# 04_-_POWER_HARVESTING_SYSTEM.net
KiCad netlist of a schematic drawn in Altium Designer
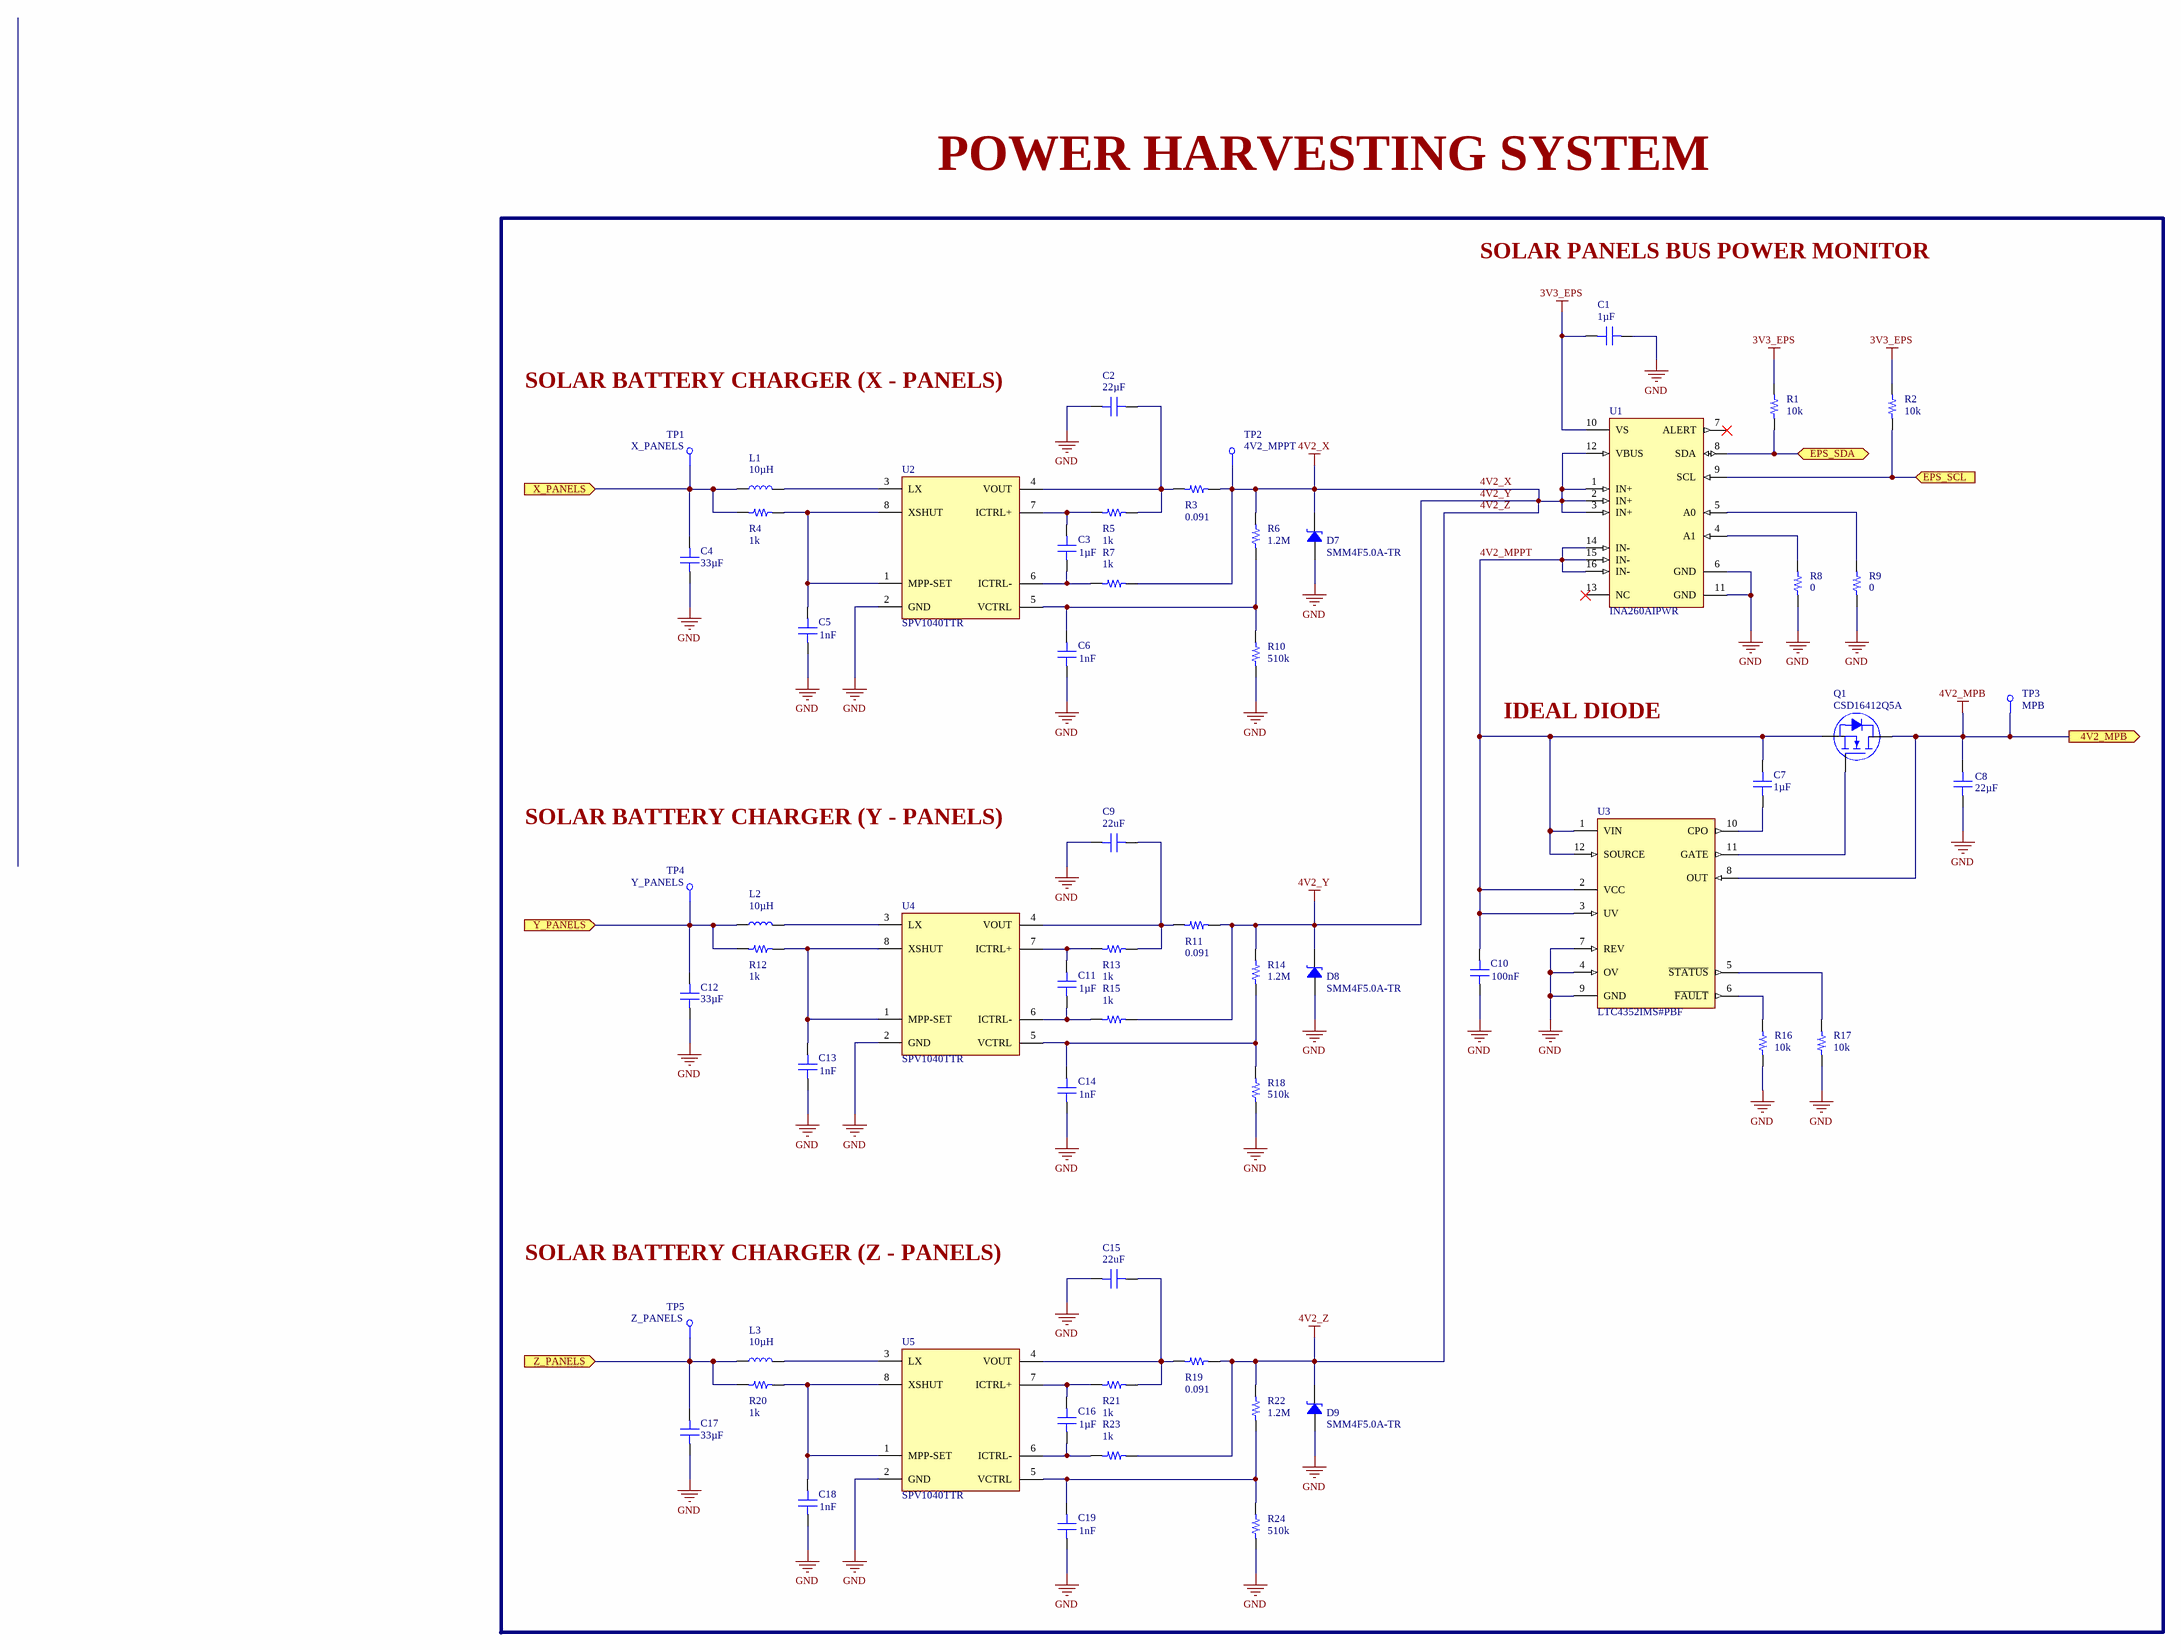
[diagram p0: [04] - POWER HARVESTING SYSTEM.SchDoc]

(export (version "E")
  (design (tool "Eeschema 10.0.6"))
  (components
    (comp (ref "C1")
      (value "CL10A105KP8NNNC")
      (footprint "CAP 0603/1608")
      (description "CAP CER 1UF 10V X5R 0603")
      (fields
        (field (name "MANUFACTURER") "Samsung")
        (field (name "TOLERANCE") "10%")
        (field (name "CAPACITANCE") "1µF")
      )
      (libsource (lib "UVG") (part "CL10A105KP8NNNC"))
    )
    (comp (ref "C2")
      (value "CL21A226MQQNNNE")
      (footprint "CAP 0805/2012")
      (description "CAP CER 22UF 6.3V X5R 0805")
      (fields
        (field (name "MANUFACTURER") "Samsung")
        (field (name "CAPACITANCE") "22µF")
        (field (name "TOLERANCE") "20%")
      )
      (libsource (lib "UVG") (part "CL21A226MQQNNNE"))
    )
    (comp (ref "C3")
      (value "CL10A105KP8NNNC")
      (footprint "CAP 0603/1608")
      (description "CAP CER 1UF 10V X5R 0603")
      (fields
        (field (name "MANUFACTURER") "Samsung")
        (field (name "TOLERANCE") "10%")
        (field (name "CAPACITANCE") "1µF")
      )
      (libsource (lib "UVG") (part "CL10A105KP8NNNC"))
    )
    (comp (ref "C4")
      (value "GRM21BR60G336ME15L")
      (footprint "CAP 0805/2012")
      (description "CAP CER 33UF 4V X5R 0805")
      (fields
        (field (name "MANUFACTURER") "Murata")
        (field (name "TOLERANCE") "20%")
        (field (name "CAPACITANCE") "33µF")
      )
      (libsource (lib "UVG") (part "GRM21BR60G336ME15L"))
    )
    (comp (ref "C5")
      (value "CL10C102JB8NNNC")
      (footprint "CAP 0603/1608")
      (description "CAP CER 1000PF 50V C0G/NP0 0603")
      (fields
        (field (name "MANUFACTURER") "Samsung")
        (field (name "TOLERANCE") "5%")
        (field (name "CAPACITANCE") "1nF")
      )
      (libsource (lib "UVG") (part "CL10C102JB8NNNC"))
    )
    (comp (ref "C6")
      (value "CL10C102JB8NNNC")
      (footprint "CAP 0603/1608")
      (description "CAP CER 1000PF 50V C0G/NP0 0603")
      (fields
        (field (name "MANUFACTURER") "Samsung")
        (field (name "TOLERANCE") "5%")
        (field (name "CAPACITANCE") "1nF")
      )
      (libsource (lib "UVG") (part "CL10C102JB8NNNC"))
    )
    (comp (ref "C7")
      (value "CL10A105KP8NNNC")
      (footprint "CAP 0603/1608")
      (description "CAP CER 1UF 10V X5R 0603")
      (fields
        (field (name "MANUFACTURER") "Samsung")
        (field (name "TOLERANCE") "10%")
        (field (name "CAPACITANCE") "1µF")
      )
      (libsource (lib "UVG") (part "CL10A105KP8NNNC"))
    )
    (comp (ref "C8")
      (value "GRM188R60J226MEA0D")
      (footprint "CAP 0603/1608")
      (description "CAP CER 22UF 6.3V X5R 0603")
      (fields
        (field (name "MANUFACTURER") "Murata")
        (field (name "CAPACITANCE") "22µF")
        (field (name "TOLERANCE") "20%")
      )
      (libsource (lib "UVG") (part "GRM188R60J226MEA0D"))
    )
    (comp (ref "C9")
      (value "CL21A226MQQNNNE")
      (footprint "CAP 0805/2012")
      (description "CAP CER 22UF 6.3V X5R 0805")
      (fields
        (field (name "MANUFACTURER") "Samsung")
        (field (name "CAPACITANCE") "22uF")
        (field (name "TOLERANCE") "20%")
      )
      (libsource (lib "UVG") (part "CL21A226MQQNNNE"))
    )
    (comp (ref "C10")
      (value "C0603C104K8RACTU")
      (footprint "CAP 0603/1608")
      (description "CAP CER 0.1UF 10V X7R 0603")
      (fields
        (field (name "MANUFACTURER") "KEMET")
        (field (name "CAPACITANCE") "100nF")
        (field (name "TOLERANCE") "10%")
      )
      (libsource (lib "UVG") (part "C0603C104K8RACTU"))
    )
    (comp (ref "C11")
      (value "CL10A105KP8NNNC")
      (footprint "CAP 0603/1608")
      (description "CAP CER 1UF 10V X5R 0603")
      (fields
        (field (name "MANUFACTURER") "Samsung")
        (field (name "TOLERANCE") "10%")
        (field (name "CAPACITANCE") "1µF")
      )
      (libsource (lib "UVG") (part "CL10A105KP8NNNC"))
    )
    (comp (ref "C12")
      (value "GRM21BR60G336ME15L")
      (footprint "CAP 0805/2012")
      (description "CAP CER 33UF 4V X5R 0805")
      (fields
        (field (name "MANUFACTURER") "Murata")
        (field (name "TOLERANCE") "20%")
        (field (name "CAPACITANCE") "33µF")
      )
      (libsource (lib "UVG") (part "GRM21BR60G336ME15L"))
    )
    (comp (ref "C13")
      (value "CL10C102JB8NNNC")
      (footprint "CAP 0603/1608")
      (description "CAP CER 1000PF 50V C0G/NP0 0603")
      (fields
        (field (name "MANUFACTURER") "Samsung")
        (field (name "TOLERANCE") "5%")
        (field (name "CAPACITANCE") "1nF")
      )
      (libsource (lib "UVG") (part "CL10C102JB8NNNC"))
    )
    (comp (ref "C14")
      (value "CL10C102JB8NNNC")
      (footprint "CAP 0603/1608")
      (description "CAP CER 1000PF 50V C0G/NP0 0603")
      (fields
        (field (name "MANUFACTURER") "Samsung")
        (field (name "TOLERANCE") "5%")
        (field (name "CAPACITANCE") "1nF")
      )
      (libsource (lib "UVG") (part "CL10C102JB8NNNC"))
    )
    (comp (ref "C15")
      (value "CL21A226MQQNNNE")
      (footprint "CAP 0805/2012")
      (description "CAP CER 22UF 6.3V X5R 0805")
      (fields
        (field (name "MANUFACTURER") "Samsung")
        (field (name "CAPACITANCE") "22uF")
        (field (name "TOLERANCE") "20%")
      )
      (libsource (lib "UVG") (part "CL21A226MQQNNNE"))
    )
    (comp (ref "C16")
      (value "CL10A105KP8NNNC")
      (footprint "CAP 0603/1608")
      (description "CAP CER 1UF 10V X5R 0603")
      (fields
        (field (name "MANUFACTURER") "Samsung")
        (field (name "TOLERANCE") "10%")
        (field (name "CAPACITANCE") "1µF")
      )
      (libsource (lib "UVG") (part "CL10A105KP8NNNC"))
    )
    (comp (ref "C17")
      (value "GRM21BR60G336ME15L")
      (footprint "CAP 0805/2012")
      (description "CAP CER 33UF 4V X5R 0805")
      (fields
        (field (name "MANUFACTURER") "Murata")
        (field (name "TOLERANCE") "20%")
        (field (name "CAPACITANCE") "33µF")
      )
      (libsource (lib "UVG") (part "GRM21BR60G336ME15L"))
    )
    (comp (ref "C18")
      (value "CL10C102JB8NNNC")
      (footprint "CAP 0603/1608")
      (description "CAP CER 1000PF 50V C0G/NP0 0603")
      (fields
        (field (name "MANUFACTURER") "Samsung")
        (field (name "TOLERANCE") "5%")
        (field (name "CAPACITANCE") "1nF")
      )
      (libsource (lib "UVG") (part "CL10C102JB8NNNC"))
    )
    (comp (ref "C19")
      (value "CL10C102JB8NNNC")
      (footprint "CAP 0603/1608")
      (description "CAP CER 1000PF 50V C0G/NP0 0603")
      (fields
        (field (name "MANUFACTURER") "Samsung")
        (field (name "TOLERANCE") "5%")
        (field (name "CAPACITANCE") "1nF")
      )
      (libsource (lib "UVG") (part "CL10C102JB8NNNC"))
    )
    (comp (ref "D7")
      (value "SMM4F5.0A-TR")
      (footprint "DO216-AA")
      (description "Diode TVS Single Uni-Dir 5V 400W 2-Pin DO-222AA T/R")
      (fields (field (name "MANUFACTURER") "STMicroelectronics"))
      (libsource (lib "UVG") (part "SMM4F5.0A-TR"))
    )
    (comp (ref "D8")
      (value "SMM4F5.0A-TR")
      (footprint "DO216-AA")
      (description "Diode TVS Single Uni-Dir 5V 400W 2-Pin DO-222AA T/R")
      (fields (field (name "MANUFACTURER") "STMicroelectronics"))
      (libsource (lib "UVG") (part "SMM4F5.0A-TR"))
    )
    (comp (ref "D9")
      (value "SMM4F5.0A-TR")
      (footprint "DO216-AA")
      (description "Diode TVS Single Uni-Dir 5V 400W 2-Pin DO-222AA T/R")
      (fields (field (name "MANUFACTURER") "STMicroelectronics"))
      (libsource (lib "UVG") (part "SMM4F5.0A-TR"))
    )
    (comp (ref "L1")
      (value "SRR1206-100ML")
      (footprint "SRR1206")
      (description "FIXED IND 10UH 3.3A 35 MOHM SMD")
      (fields
        (field (name "MANUFACTURER") "Bourns")
        (field (name "TOLERANCE") "20%")
        (field (name "INDUCTANCE") "10µH")
      )
      (libsource (lib "UVG") (part "SRR1206-100ML"))
    )
    (comp (ref "L2")
      (value "SRR1206-100ML")
      (footprint "SRR1206")
      (description "FIXED IND 10UH 3.3A 35 MOHM SMD")
      (fields
        (field (name "MANUFACTURER") "Bourns")
        (field (name "TOLERANCE") "20%")
        (field (name "INDUCTANCE") "10µH")
      )
      (libsource (lib "UVG") (part "SRR1206-100ML"))
    )
    (comp (ref "L3")
      (value "SRR1206-100ML")
      (footprint "SRR1206")
      (description "FIXED IND 10UH 3.3A 35 MOHM SMD")
      (fields
        (field (name "MANUFACTURER") "Bourns")
        (field (name "TOLERANCE") "20%")
        (field (name "INDUCTANCE") "10µH")
      )
      (libsource (lib "UVG") (part "SRR1206-100ML"))
    )
    (comp (ref "Q1")
      (value "CSD16412Q5A")
      (footprint "8-VSONP (5x6)")
      (description "MOSFET N-CH 25V 52A 8SON")
      (fields (field (name "MANUFACTURER") "Texas Instruments"))
      (libsource (lib "UVG") (part "CSD16412Q5A"))
    )
    (comp (ref "R1")
      (value "RNCP0603FTD10K0")
      (footprint "RES 0603/1608")
      (description "RES SMD 10K OHM 1% 1/8W 0603")
      (fields
        (field (name "MANUFACTURER") "Stackpole Electronics")
        (field (name "RESISTANCE") "10k")
        (field (name "TOLERANCE") "1%")
      )
      (libsource (lib "UVG") (part "RNCP0603FTD10K0"))
    )
    (comp (ref "R2")
      (value "RNCP0603FTD10K0")
      (footprint "RES 0603/1608")
      (description "RES SMD 10K OHM 1% 1/8W 0603")
      (fields
        (field (name "MANUFACTURER") "Stackpole Electronics")
        (field (name "RESISTANCE") "10k")
        (field (name "TOLERANCE") "1%")
      )
      (libsource (lib "UVG") (part "RNCP0603FTD10K0"))
    )
    (comp (ref "R3")
      (value "RLP73N3AR091FTDF")
      (footprint "STACKPOLE CSRN2512")
      (description "RES SMD 0.091 OHM 1% 2W 2512")
      (fields
        (field (name "MANUFACTURER") "TE Connectivity")
        (field (name "MANUFACTURER PART NUMBER") "2-2176057-4")
        (field (name "RESISTANCE") "0.091")
      )
      (libsource (lib "UVG") (part "RLP73N3AR091FTDF"))
    )
    (comp (ref "R4")
      (value "ESR03EZPJ102")
      (footprint "RES 0603/1608")
      (description "RES SMD 1K OHM 5% 1/4W 0603")
      (fields
        (field (name "MANUFACTURER") "Rohm")
        (field (name "RESISTANCE") "1k")
        (field (name "TOLERANCE") "5%")
      )
      (libsource (lib "UVG") (part "ESR03EZPJ102"))
    )
    (comp (ref "R5")
      (value "ESR03EZPJ102")
      (footprint "RES 0603/1608")
      (description "RES SMD 1K OHM 5% 1/4W 0603")
      (fields
        (field (name "MANUFACTURER") "Rohm")
        (field (name "RESISTANCE") "1k")
        (field (name "TOLERANCE") "5%")
      )
      (libsource (lib "UVG") (part "ESR03EZPJ102"))
    )
    (comp (ref "R6")
      (value "RC0603JR-071M2L")
      (footprint "RES 0603/1608")
      (description "RES SMD 1.2M OHM 5% 1/10W 0603")
      (fields
        (field (name "MANUFACTURER") "Yageo")
        (field (name "RESISTANCE") "1.2M")
        (field (name "TOLERANCE") "5%")
      )
      (libsource (lib "UVG") (part "RC0603JR-071M2L"))
    )
    (comp (ref "R7")
      (value "ESR03EZPJ102")
      (footprint "RES 0603/1608")
      (description "RES SMD 1K OHM 5% 1/4W 0603")
      (fields
        (field (name "MANUFACTURER") "Rohm")
        (field (name "RESISTANCE") "1k")
        (field (name "TOLERANCE") "5%")
      )
      (libsource (lib "UVG") (part "ESR03EZPJ102"))
    )
    (comp (ref "R8")
      (value "RMCF0603ZT0R00")
      (footprint "RES 0603/1608")
      (description "RES SMD 0 OHM JUMPER 1/10W 0603")
      (fields (field (name "MANUFACTURER") "Stackpole Electronics") (field (name "RESISTANCE") "0"))
      (libsource (lib "UVG") (part "RMCF0603ZT0R00"))
    )
    (comp (ref "R9")
      (value "RMCF0603ZT0R00")
      (footprint "RES 0603/1608")
      (description "RES SMD 0 OHM JUMPER 1/10W 0603")
      (fields (field (name "MANUFACTURER") "Stackpole Electronics") (field (name "RESISTANCE") "0"))
      (libsource (lib "UVG") (part "RMCF0603ZT0R00"))
    )
    (comp (ref "R10")
      (value "RMCF0603FT510K")
      (footprint "RES 0603/1608")
      (description "RES SMD 510K OHM 1% 1/10W 0603")
      (fields
        (field (name "MANUFACTURER") "Stackpole Electronics")
        (field (name "RESISTANCE") "510k")
        (field (name "TOLERANCE") "1%")
      )
      (libsource (lib "UVG") (part "RMCF0603FT510K"))
    )
    (comp (ref "R11")
      (value "RLP73N3AR091FTDF")
      (footprint "STACKPOLE CSRN2512")
      (description "RES SMD 0.091 OHM 1% 2W 2512")
      (fields
        (field (name "MANUFACTURER") "TE Connectivity")
        (field (name "MANUFACTURER PART NUMBER") "2-2176057-4")
        (field (name "RESISTANCE") "0.091")
      )
      (libsource (lib "UVG") (part "RLP73N3AR091FTDF"))
    )
    (comp (ref "R12")
      (value "ESR03EZPJ102")
      (footprint "RES 0603/1608")
      (description "RES SMD 1K OHM 5% 1/4W 0603")
      (fields
        (field (name "MANUFACTURER") "Rohm")
        (field (name "RESISTANCE") "1k")
        (field (name "TOLERANCE") "5%")
      )
      (libsource (lib "UVG") (part "ESR03EZPJ102"))
    )
    (comp (ref "R13")
      (value "ESR03EZPJ102")
      (footprint "RES 0603/1608")
      (description "RES SMD 1K OHM 5% 1/4W 0603")
      (fields
        (field (name "MANUFACTURER") "Rohm")
        (field (name "RESISTANCE") "1k")
        (field (name "TOLERANCE") "5%")
      )
      (libsource (lib "UVG") (part "ESR03EZPJ102"))
    )
    (comp (ref "R14")
      (value "RC0603JR-071M2L")
      (footprint "RES 0603/1608")
      (description "RES SMD 1.2M OHM 5% 1/10W 0603")
      (fields
        (field (name "MANUFACTURER") "Yageo")
        (field (name "RESISTANCE") "1.2M")
        (field (name "TOLERANCE") "5%")
      )
      (libsource (lib "UVG") (part "RC0603JR-071M2L"))
    )
    (comp (ref "R15")
      (value "ESR03EZPJ102")
      (footprint "RES 0603/1608")
      (description "RES SMD 1K OHM 5% 1/4W 0603")
      (fields
        (field (name "MANUFACTURER") "Rohm")
        (field (name "RESISTANCE") "1k")
        (field (name "TOLERANCE") "5%")
      )
      (libsource (lib "UVG") (part "ESR03EZPJ102"))
    )
    (comp (ref "R16")
      (value "RNCP0603FTD10K0")
      (footprint "RES 0603/1608")
      (description "RES SMD 10K OHM 1% 1/8W 0603")
      (fields
        (field (name "MANUFACTURER") "Stackpole Electronics")
        (field (name "RESISTANCE") "10k")
        (field (name "TOLERANCE") "1%")
      )
      (libsource (lib "UVG") (part "RNCP0603FTD10K0"))
    )
    (comp (ref "R17")
      (value "RNCP0603FTD10K0")
      (footprint "RES 0603/1608")
      (description "RES SMD 10K OHM 1% 1/8W 0603")
      (fields
        (field (name "MANUFACTURER") "Stackpole Electronics")
        (field (name "RESISTANCE") "10k")
        (field (name "TOLERANCE") "1%")
      )
      (libsource (lib "UVG") (part "RNCP0603FTD10K0"))
    )
    (comp (ref "R18")
      (value "RMCF0603FT510K")
      (footprint "RES 0603/1608")
      (description "RES SMD 510K OHM 1% 1/10W 0603")
      (fields
        (field (name "MANUFACTURER") "Stackpole Electronics")
        (field (name "RESISTANCE") "510k")
        (field (name "TOLERANCE") "1%")
      )
      (libsource (lib "UVG") (part "RMCF0603FT510K"))
    )
    (comp (ref "R19")
      (value "RLP73N3AR091FTDF")
      (footprint "STACKPOLE CSRN2512")
      (description "RES SMD 0.091 OHM 1% 2W 2512")
      (fields
        (field (name "MANUFACTURER") "TE Connectivity")
        (field (name "MANUFACTURER PART NUMBER") "2-2176057-4")
        (field (name "RESISTANCE") "0.091")
      )
      (libsource (lib "UVG") (part "RLP73N3AR091FTDF"))
    )
    (comp (ref "R20")
      (value "ESR03EZPJ102")
      (footprint "RES 0603/1608")
      (description "RES SMD 1K OHM 5% 1/4W 0603")
      (fields
        (field (name "MANUFACTURER") "Rohm")
        (field (name "RESISTANCE") "1k")
        (field (name "TOLERANCE") "5%")
      )
      (libsource (lib "UVG") (part "ESR03EZPJ102"))
    )
    (comp (ref "R21")
      (value "ESR03EZPJ102")
      (footprint "RES 0603/1608")
      (description "RES SMD 1K OHM 5% 1/4W 0603")
      (fields
        (field (name "MANUFACTURER") "Rohm")
        (field (name "RESISTANCE") "1k")
        (field (name "TOLERANCE") "5%")
      )
      (libsource (lib "UVG") (part "ESR03EZPJ102"))
    )
    (comp (ref "R22")
      (value "RC0603JR-071M2L")
      (footprint "RES 0603/1608")
      (description "RES SMD 1.2M OHM 5% 1/10W 0603")
      (fields
        (field (name "MANUFACTURER") "Yageo")
        (field (name "RESISTANCE") "1.2M")
        (field (name "TOLERANCE") "5%")
      )
      (libsource (lib "UVG") (part "RC0603JR-071M2L"))
    )
    (comp (ref "R23")
      (value "ESR03EZPJ102")
      (footprint "RES 0603/1608")
      (description "RES SMD 1K OHM 5% 1/4W 0603")
      (fields
        (field (name "MANUFACTURER") "Rohm")
        (field (name "RESISTANCE") "1k")
        (field (name "TOLERANCE") "5%")
      )
      (libsource (lib "UVG") (part "ESR03EZPJ102"))
    )
    (comp (ref "R24")
      (value "RMCF0603FT510K")
      (footprint "RES 0603/1608")
      (description "RES SMD 510K OHM 1% 1/10W 0603")
      (fields
        (field (name "MANUFACTURER") "Stackpole Electronics")
        (field (name "RESISTANCE") "510k")
        (field (name "TOLERANCE") "1%")
      )
      (libsource (lib "UVG") (part "RMCF0603FT510K"))
    )
    (comp (ref "TP1")
      (value "X_PANELS")
      (footprint "Testpoint")
      (description "GENERIC TESTPOINT")
      (libsource (lib "UVG") (part "TESTPOINT"))
    )
    (comp (ref "TP2")
      (value "4V2_MPPT")
      (footprint "Testpoint")
      (description "GENERIC TESTPOINT")
      (libsource (lib "UVG") (part "TESTPOINT"))
    )
    (comp (ref "TP3")
      (value "MPB")
      (footprint "Testpoint")
      (description "GENERIC TESTPOINT")
      (libsource (lib "UVG") (part "TESTPOINT"))
    )
    (comp (ref "TP4")
      (value "Y_PANELS")
      (footprint "Testpoint")
      (description "GENERIC TESTPOINT")
      (libsource (lib "UVG") (part "TESTPOINT"))
    )
    (comp (ref "TP5")
      (value "Z_PANELS")
      (footprint "Testpoint")
      (description "GENERIC TESTPOINT")
      (libsource (lib "UVG") (part "TESTPOINT"))
    )
    (comp (ref "U1")
      (value "INA260AIPWR")
      (footprint "TSOP65P640X120-16N")
      (description "IC MONITOR PWR/CURR 16TSSOP")
      (fields (field (name "MANUFACTURER") "Texas Instruments"))
      (libsource (lib "UVG") (part "INA260AIPWR"))
    )
    (comp (ref "U2")
      (value "SPV1040TTR")
      (footprint "TSOP65P630X120-8N")
      (description "IC SOLAR BATTERY CHARGER 8TSSOP")
      (fields (field (name "MANUFACTURER") "STMicroelectronics"))
      (libsource (lib "UVG") (part "SPV1040TTR"))
    )
    (comp (ref "U3")
      (value "LTC4352IMS#PBF")
      (footprint "MSOP-12")
      (description "IC OR CTRLR N+1 12MSOP")
      (fields (field (name "MANUFACTURER") "Analog Devices / Linear Technology"))
      (libsource (lib "UVG") (part "LTC4352IMS#PBF"))
    )
    (comp (ref "U4")
      (value "SPV1040TTR")
      (footprint "TSOP65P630X120-8N")
      (description "IC SOLAR BATTERY CHARGER 8TSSOP")
      (fields (field (name "MANUFACTURER") "STMicroelectronics"))
      (libsource (lib "UVG") (part "SPV1040TTR"))
    )
    (comp (ref "U5")
      (value "SPV1040TTR")
      (footprint "TSOP65P630X120-8N")
      (description "IC SOLAR BATTERY CHARGER 8TSSOP")
      (fields (field (name "MANUFACTURER") "STMicroelectronics"))
      (libsource (lib "UVG") (part "SPV1040TTR"))
    )
  )
  (nets
    (net (code "1") (name "/4V2_MPPT") (class "Default")
      (node (ref "C10") (pin "2") (pinfunction "2_2") (pintype "passive"))
      (node (ref "C7") (pin "2") (pinfunction "2_2") (pintype "passive"))
      (node (ref "Q1") (pin "S") (pinfunction "S_S") (pintype "passive"))
      (node (ref "U1") (pin "14") (pinfunction "IN-_14") (pintype "input"))
      (node (ref "U1") (pin "15") (pinfunction "IN-_15") (pintype "input"))
      (node (ref "U1") (pin "16") (pinfunction "IN-_16") (pintype "input"))
      (node (ref "U3") (pin "1") (pinfunction "VIN_1") (pintype "power_in"))
      (node (ref "U3") (pin "12") (pinfunction "SOURCE_12") (pintype "input"))
      (node (ref "U3") (pin "2") (pinfunction "VCC_2") (pintype "power_in"))
      (node (ref "U3") (pin "3") (pinfunction "UV_3") (pintype "input"))
    )
    (net (code "2") (name "/EPS_SCL") (class "Default")
      (node (ref "R2") (pin "1") (pinfunction "1_1") (pintype "passive"))
      (node (ref "U1") (pin "9") (pinfunction "SCL_9") (pintype "input"))
    )
    (net (code "3") (name "/EPS_SDA") (class "Default")
      (node (ref "R1") (pin "1") (pinfunction "1_1") (pintype "passive"))
      (node (ref "U1") (pin "8") (pinfunction "SDA_8") (pintype "bidirectional"))
    )
    (net (code "4") (name "/X_PANELS") (class "Default")
      (node (ref "C4") (pin "2") (pinfunction "2_2") (pintype "passive"))
      (node (ref "L1") (pin "1") (pinfunction "1_1") (pintype "passive"))
      (node (ref "R4") (pin "1") (pinfunction "1_1") (pintype "passive"))
      (node (ref "TP1") (pin "1") (pinfunction "1_1") (pintype "passive"))
    )
    (net (code "5") (name "/Y_PANELS") (class "Default")
      (node (ref "C12") (pin "2") (pinfunction "2_2") (pintype "passive"))
      (node (ref "L2") (pin "1") (pinfunction "1_1") (pintype "passive"))
      (node (ref "R12") (pin "1") (pinfunction "1_1") (pintype "passive"))
      (node (ref "TP4") (pin "1") (pinfunction "1_1") (pintype "passive"))
    )
    (net (code "6") (name "/Z_PANELS") (class "Default")
      (node (ref "C17") (pin "2") (pinfunction "2_2") (pintype "passive"))
      (node (ref "L3") (pin "1") (pinfunction "1_1") (pintype "passive"))
      (node (ref "R20") (pin "1") (pinfunction "1_1") (pintype "passive"))
      (node (ref "TP5") (pin "1") (pinfunction "1_1") (pintype "passive"))
    )
    (net (code "7") (name "3V3_EPS") (class "Default")
      (node (ref "C1") (pin "1") (pinfunction "1_1") (pintype "passive"))
      (node (ref "R1") (pin "2") (pinfunction "2_2") (pintype "passive"))
      (node (ref "R2") (pin "2") (pinfunction "2_2") (pintype "passive"))
      (node (ref "U1") (pin "10") (pinfunction "VS_10") (pintype "power_in"))
    )
    (net (code "8") (name "4V2_MPB") (class "Default")
      (node (ref "C8") (pin "2") (pinfunction "2_2") (pintype "passive"))
      (node (ref "Q1") (pin "D") (pinfunction "D_D") (pintype "passive"))
      (node (ref "TP3") (pin "1") (pinfunction "1_1") (pintype "passive"))
      (node (ref "U3") (pin "8") (pinfunction "OUT_8") (pintype "input"))
    )
    (net (code "9") (name "4V2_X") (class "Default")
      (node (ref "D7") (pin "K") (pinfunction "2_K") (pintype "passive"))
      (node (ref "D8") (pin "K") (pinfunction "2_K") (pintype "passive"))
      (node (ref "D9") (pin "K") (pinfunction "2_K") (pintype "passive"))
      (node (ref "R11") (pin "2") (pinfunction "2_2") (pintype "passive"))
      (node (ref "R14") (pin "2") (pinfunction "2_2") (pintype "passive"))
      (node (ref "R15") (pin "2") (pinfunction "2_2") (pintype "passive"))
      (node (ref "R19") (pin "2") (pinfunction "2_2") (pintype "passive"))
      (node (ref "R22") (pin "2") (pinfunction "2_2") (pintype "passive"))
      (node (ref "R23") (pin "2") (pinfunction "2_2") (pintype "passive"))
      (node (ref "R3") (pin "2") (pinfunction "2_2") (pintype "passive"))
      (node (ref "R6") (pin "2") (pinfunction "2_2") (pintype "passive"))
      (node (ref "R7") (pin "2") (pinfunction "2_2") (pintype "passive"))
      (node (ref "TP2") (pin "1") (pinfunction "1_1") (pintype "passive"))
      (node (ref "U1") (pin "1") (pinfunction "IN+_1") (pintype "input"))
      (node (ref "U1") (pin "12") (pinfunction "VBUS_12") (pintype "input"))
      (node (ref "U1") (pin "2") (pinfunction "IN+_2") (pintype "input"))
      (node (ref "U1") (pin "3") (pinfunction "IN+_3") (pintype "input"))
    )
    (net (code "10") (name "GND") (class "Default")
      (node (ref "C1") (pin "2") (pinfunction "2_2") (pintype "passive"))
      (node (ref "C10") (pin "1") (pinfunction "1_1") (pintype "passive"))
      (node (ref "C12") (pin "1") (pinfunction "1_1") (pintype "passive"))
      (node (ref "C13") (pin "1") (pinfunction "1_1") (pintype "passive"))
      (node (ref "C14") (pin "1") (pinfunction "1_1") (pintype "passive"))
      (node (ref "C15") (pin "2") (pinfunction "2_2") (pintype "passive"))
      (node (ref "C17") (pin "1") (pinfunction "1_1") (pintype "passive"))
      (node (ref "C18") (pin "1") (pinfunction "1_1") (pintype "passive"))
      (node (ref "C19") (pin "1") (pinfunction "1_1") (pintype "passive"))
      (node (ref "C2") (pin "2") (pinfunction "2_2") (pintype "passive"))
      (node (ref "C4") (pin "1") (pinfunction "1_1") (pintype "passive"))
      (node (ref "C5") (pin "1") (pinfunction "1_1") (pintype "passive"))
      (node (ref "C6") (pin "1") (pinfunction "1_1") (pintype "passive"))
      (node (ref "C8") (pin "1") (pinfunction "1_1") (pintype "passive"))
      (node (ref "C9") (pin "2") (pinfunction "2_2") (pintype "passive"))
      (node (ref "D7") (pin "A") (pinfunction "1_A") (pintype "passive"))
      (node (ref "D8") (pin "A") (pinfunction "1_A") (pintype "passive"))
      (node (ref "D9") (pin "A") (pinfunction "1_A") (pintype "passive"))
      (node (ref "R10") (pin "1") (pinfunction "1_1") (pintype "passive"))
      (node (ref "R16") (pin "1") (pinfunction "1_1") (pintype "passive"))
      (node (ref "R17") (pin "1") (pinfunction "1_1") (pintype "passive"))
      (node (ref "R18") (pin "1") (pinfunction "1_1") (pintype "passive"))
      (node (ref "R24") (pin "1") (pinfunction "1_1") (pintype "passive"))
      (node (ref "R8") (pin "1") (pinfunction "1_1") (pintype "passive"))
      (node (ref "R9") (pin "1") (pinfunction "1_1") (pintype "passive"))
      (node (ref "U1") (pin "11") (pinfunction "GND_11") (pintype "power_in"))
      (node (ref "U1") (pin "6") (pinfunction "GND_6") (pintype "power_in"))
      (node (ref "U2") (pin "2") (pinfunction "GND_2") (pintype "power_in"))
      (node (ref "U3") (pin "4") (pinfunction "OV_4") (pintype "input"))
      (node (ref "U3") (pin "7") (pinfunction "REV_7") (pintype "input"))
      (node (ref "U3") (pin "9") (pinfunction "GND_9") (pintype "power_in"))
      (node (ref "U4") (pin "2") (pinfunction "GND_2") (pintype "power_in"))
      (node (ref "U5") (pin "2") (pinfunction "GND_2") (pintype "power_in"))
    )
    (net (code "11") (name "Net-(U1-A0)") (class "Default")
      (node (ref "R9") (pin "2") (pinfunction "2_2") (pintype "passive"))
      (node (ref "U1") (pin "5") (pinfunction "A0_5") (pintype "input"))
    )
    (net (code "12") (name "Net-(U1-A1)") (class "Default")
      (node (ref "R8") (pin "2") (pinfunction "2_2") (pintype "passive"))
      (node (ref "U1") (pin "4") (pinfunction "A1_4") (pintype "input"))
    )
    (net (code "13") (name "Net-(U2-ICTRL+)") (class "Default")
      (node (ref "C3") (pin "2") (pinfunction "2_2") (pintype "passive"))
      (node (ref "R5") (pin "1") (pinfunction "1_1") (pintype "passive"))
      (node (ref "U2") (pin "7") (pinfunction "ICTRL+_7") (pintype "passive"))
    )
    (net (code "14") (name "Net-(U2-ICTRL-)") (class "Default")
      (node (ref "C3") (pin "1") (pinfunction "1_1") (pintype "passive"))
      (node (ref "R7") (pin "1") (pinfunction "1_1") (pintype "passive"))
      (node (ref "U2") (pin "6") (pinfunction "ICTRL-_6") (pintype "passive"))
    )
    (net (code "15") (name "Net-(U2-LX)") (class "Default")
      (node (ref "L1") (pin "2") (pinfunction "2_2") (pintype "passive"))
      (node (ref "U2") (pin "3") (pinfunction "LX_3") (pintype "passive"))
    )
    (net (code "16") (name "Net-(U2-MPP-SET)") (class "Default")
      (node (ref "C5") (pin "2") (pinfunction "2_2") (pintype "passive"))
      (node (ref "R4") (pin "2") (pinfunction "2_2") (pintype "passive"))
      (node (ref "U2") (pin "1") (pinfunction "MPP-SET_1") (pintype "power_in"))
      (node (ref "U2") (pin "8") (pinfunction "XSHUT_8") (pintype "passive"))
    )
    (net (code "17") (name "Net-(U2-VCTRL)") (class "Default")
      (node (ref "C6") (pin "2") (pinfunction "2_2") (pintype "passive"))
      (node (ref "R10") (pin "2") (pinfunction "2_2") (pintype "passive"))
      (node (ref "R6") (pin "1") (pinfunction "1_1") (pintype "passive"))
      (node (ref "U2") (pin "5") (pinfunction "VCTRL_5") (pintype "passive"))
    )
    (net (code "18") (name "Net-(U2-VOUT)") (class "Default")
      (node (ref "C2") (pin "1") (pinfunction "1_1") (pintype "passive"))
      (node (ref "R3") (pin "1") (pinfunction "1_1") (pintype "passive"))
      (node (ref "R5") (pin "2") (pinfunction "2_2") (pintype "passive"))
      (node (ref "U2") (pin "4") (pinfunction "VOUT_4") (pintype "power_in"))
    )
    (net (code "19") (name "Net-(U3-CPO)") (class "Default")
      (node (ref "C7") (pin "1") (pinfunction "1_1") (pintype "passive"))
      (node (ref "U3") (pin "10") (pinfunction "CPO_10") (pintype "output"))
    )
    (net (code "20") (name "Net-(U3-GATE)") (class "Default")
      (node (ref "Q1") (pin "G") (pinfunction "G_G") (pintype "passive"))
      (node (ref "U3") (pin "11") (pinfunction "GATE_11") (pintype "output"))
    )
    (net (code "21") (name "Net-(U3-~{FAULT})") (class "Default")
      (node (ref "R16") (pin "2") (pinfunction "2_2") (pintype "passive"))
      (node (ref "U3") (pin "6") (pinfunction "~{FAULT}_6") (pintype "output"))
    )
    (net (code "22") (name "Net-(U3-~{STATUS})") (class "Default")
      (node (ref "R17") (pin "2") (pinfunction "2_2") (pintype "passive"))
      (node (ref "U3") (pin "5") (pinfunction "~{STATUS}_5") (pintype "output"))
    )
    (net (code "23") (name "Net-(U4-ICTRL+)") (class "Default")
      (node (ref "C11") (pin "2") (pinfunction "2_2") (pintype "passive"))
      (node (ref "R13") (pin "1") (pinfunction "1_1") (pintype "passive"))
      (node (ref "U4") (pin "7") (pinfunction "ICTRL+_7") (pintype "passive"))
    )
    (net (code "24") (name "Net-(U4-ICTRL-)") (class "Default")
      (node (ref "C11") (pin "1") (pinfunction "1_1") (pintype "passive"))
      (node (ref "R15") (pin "1") (pinfunction "1_1") (pintype "passive"))
      (node (ref "U4") (pin "6") (pinfunction "ICTRL-_6") (pintype "passive"))
    )
    (net (code "25") (name "Net-(U4-LX)") (class "Default")
      (node (ref "L2") (pin "2") (pinfunction "2_2") (pintype "passive"))
      (node (ref "U4") (pin "3") (pinfunction "LX_3") (pintype "passive"))
    )
    (net (code "26") (name "Net-(U4-MPP-SET)") (class "Default")
      (node (ref "C13") (pin "2") (pinfunction "2_2") (pintype "passive"))
      (node (ref "R12") (pin "2") (pinfunction "2_2") (pintype "passive"))
      (node (ref "U4") (pin "1") (pinfunction "MPP-SET_1") (pintype "power_in"))
      (node (ref "U4") (pin "8") (pinfunction "XSHUT_8") (pintype "passive"))
    )
    (net (code "27") (name "Net-(U4-VCTRL)") (class "Default")
      (node (ref "C14") (pin "2") (pinfunction "2_2") (pintype "passive"))
      (node (ref "R14") (pin "1") (pinfunction "1_1") (pintype "passive"))
      (node (ref "R18") (pin "2") (pinfunction "2_2") (pintype "passive"))
      (node (ref "U4") (pin "5") (pinfunction "VCTRL_5") (pintype "passive"))
    )
    (net (code "28") (name "Net-(U4-VOUT)") (class "Default")
      (node (ref "C9") (pin "1") (pinfunction "1_1") (pintype "passive"))
      (node (ref "R11") (pin "1") (pinfunction "1_1") (pintype "passive"))
      (node (ref "R13") (pin "2") (pinfunction "2_2") (pintype "passive"))
      (node (ref "U4") (pin "4") (pinfunction "VOUT_4") (pintype "power_in"))
    )
    (net (code "29") (name "Net-(U5-ICTRL+)") (class "Default")
      (node (ref "C16") (pin "2") (pinfunction "2_2") (pintype "passive"))
      (node (ref "R21") (pin "1") (pinfunction "1_1") (pintype "passive"))
      (node (ref "U5") (pin "7") (pinfunction "ICTRL+_7") (pintype "passive"))
    )
    (net (code "30") (name "Net-(U5-ICTRL-)") (class "Default")
      (node (ref "C16") (pin "1") (pinfunction "1_1") (pintype "passive"))
      (node (ref "R23") (pin "1") (pinfunction "1_1") (pintype "passive"))
      (node (ref "U5") (pin "6") (pinfunction "ICTRL-_6") (pintype "passive"))
    )
    (net (code "31") (name "Net-(U5-LX)") (class "Default")
      (node (ref "L3") (pin "2") (pinfunction "2_2") (pintype "passive"))
      (node (ref "U5") (pin "3") (pinfunction "LX_3") (pintype "passive"))
    )
    (net (code "32") (name "Net-(U5-MPP-SET)") (class "Default")
      (node (ref "C18") (pin "2") (pinfunction "2_2") (pintype "passive"))
      (node (ref "R20") (pin "2") (pinfunction "2_2") (pintype "passive"))
      (node (ref "U5") (pin "1") (pinfunction "MPP-SET_1") (pintype "power_in"))
      (node (ref "U5") (pin "8") (pinfunction "XSHUT_8") (pintype "passive"))
    )
    (net (code "33") (name "Net-(U5-VCTRL)") (class "Default")
      (node (ref "C19") (pin "2") (pinfunction "2_2") (pintype "passive"))
      (node (ref "R22") (pin "1") (pinfunction "1_1") (pintype "passive"))
      (node (ref "R24") (pin "2") (pinfunction "2_2") (pintype "passive"))
      (node (ref "U5") (pin "5") (pinfunction "VCTRL_5") (pintype "passive"))
    )
    (net (code "34") (name "Net-(U5-VOUT)") (class "Default")
      (node (ref "C15") (pin "1") (pinfunction "1_1") (pintype "passive"))
      (node (ref "R19") (pin "1") (pinfunction "1_1") (pintype "passive"))
      (node (ref "R21") (pin "2") (pinfunction "2_2") (pintype "passive"))
      (node (ref "U5") (pin "4") (pinfunction "VOUT_4") (pintype "power_in"))
    )
    (net (code "35") (name "unconnected-(U1-ALERT-Pad7)") (class "Default")
      (node (ref "U1") (pin "7") (pinfunction "ALERT_7") (pintype "output+no_connect"))
    )
    (net (code "36") (name "unconnected-(U1-NC-Pad13)") (class "Default")
      (node (ref "U1") (pin "13") (pinfunction "NC_13") (pintype "passive+no_connect"))
    )
  )
)
